# micromouse6_3.net
KiCad netlist of a schematic drawn in EAGLE
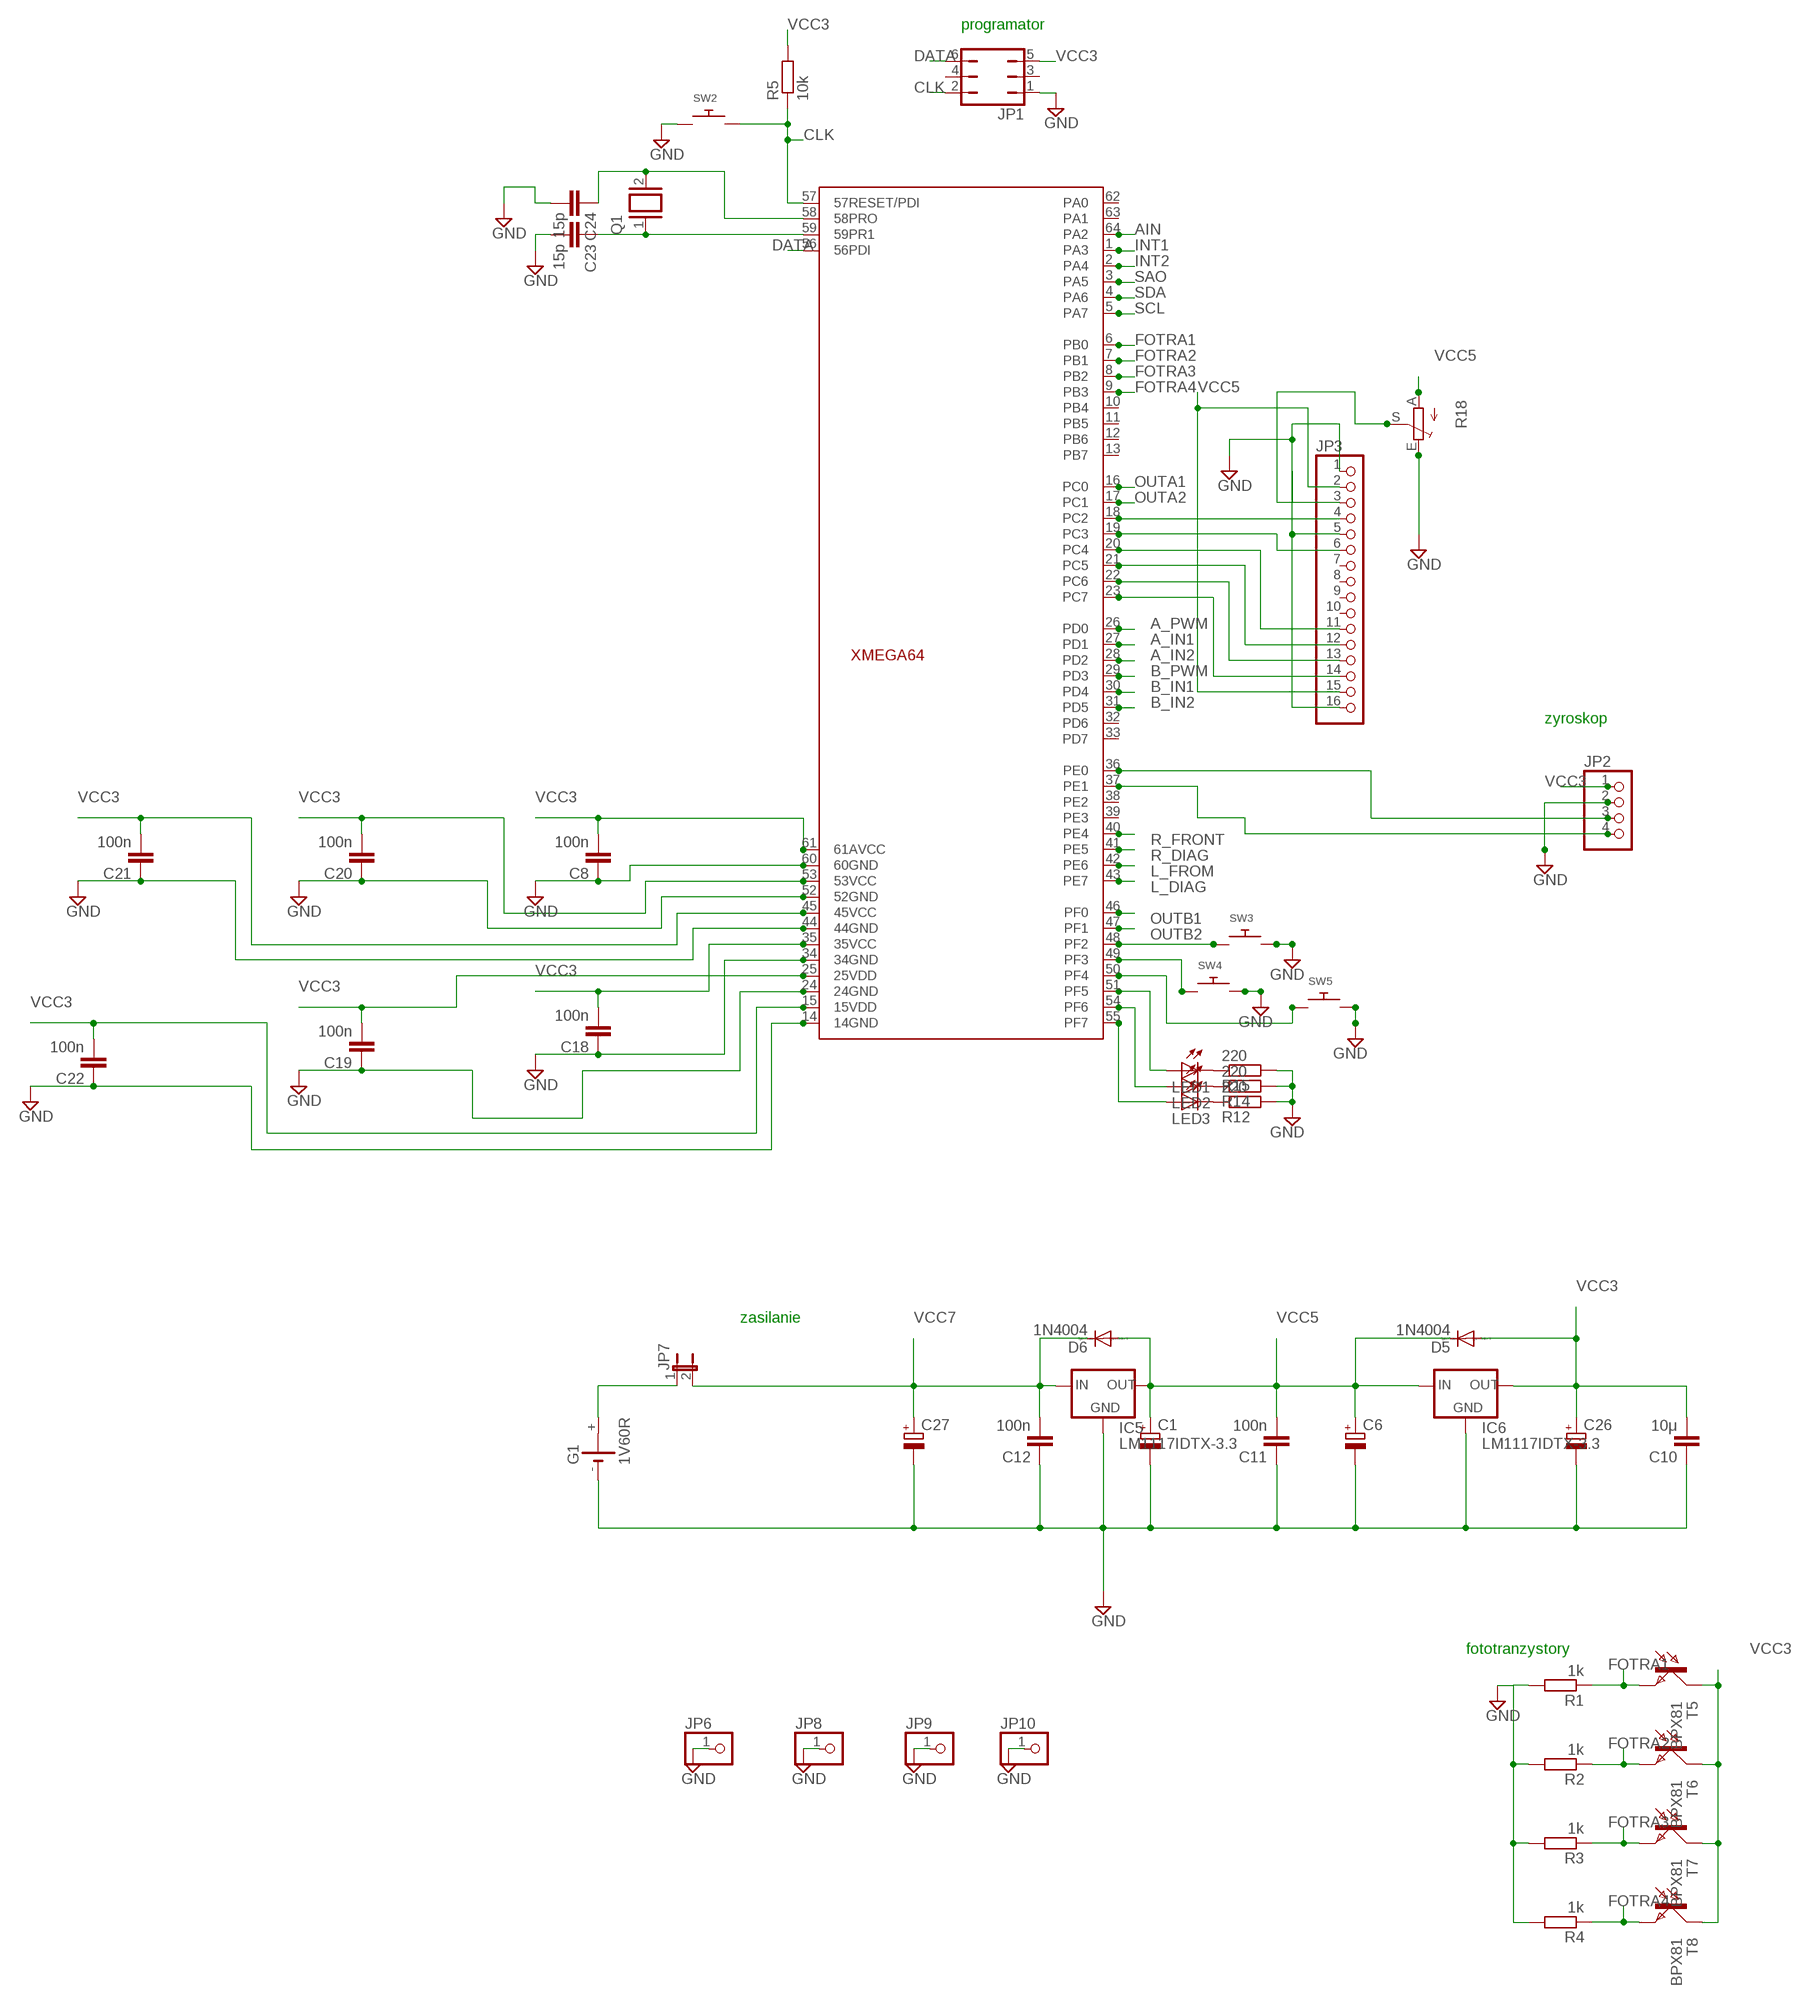
[diagram p0: schematic, sheet 1, part 1 of 2]
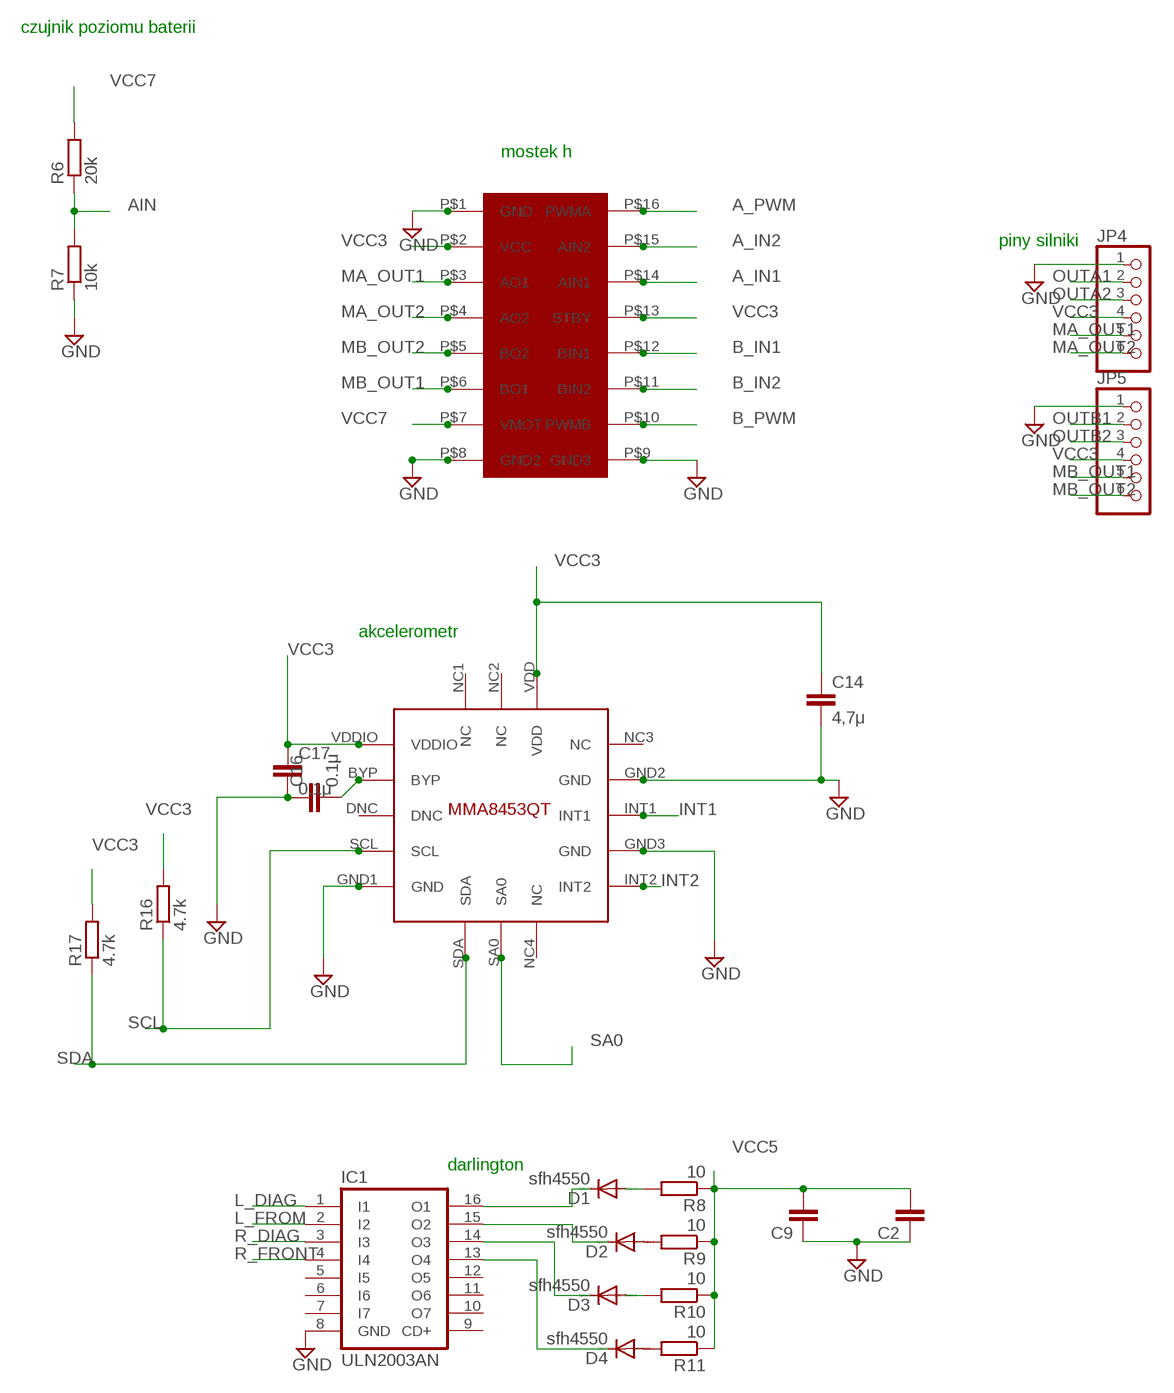
[diagram p1: schematic, sheet 1, part 2 of 2]

(export (version "E")
  (design (tool "Eeschema 10.0.6"))
  (components
    (comp (ref "ACC1")
      (value "MMA8453QT")
      (footprint "eagle-import:MMA8453QT")
      (libsource (lib "eagle-import") (part "MMA8453QT"))
    )
    (comp (ref "C1")
      (value "CPOL-EUE2.5-5")
      (footprint "eagle-import:E2,5-5")
      (libsource (lib "eagle-import") (part "CPOL-EUE2.5-5"))
    )
    (comp (ref "C2")
      (value "C-EU025-024X044")
      (footprint "eagle-import:C025-024X044")
      (libsource (lib "eagle-import") (part "C-EU025-024X044"))
    )
    (comp (ref "C6")
      (value "CPOL-EUE2.5-5")
      (footprint "eagle-import:E2,5-5")
      (libsource (lib "eagle-import") (part "CPOL-EUE2.5-5"))
    )
    (comp (ref "C8")
      (value "100n")
      (footprint "eagle-import:C025-024X044")
      (libsource (lib "eagle-import") (part "C-EU025-024X044"))
    )
    (comp (ref "C9")
      (value "C-EU025-024X044")
      (footprint "eagle-import:C025-024X044")
      (libsource (lib "eagle-import") (part "C-EU025-024X044"))
    )
    (comp (ref "C10")
      (value "10μ")
      (footprint "eagle-import:C025-024X044")
      (libsource (lib "eagle-import") (part "C-EU025-024X044"))
    )
    (comp (ref "C11")
      (value "100n")
      (footprint "eagle-import:C025-024X044")
      (libsource (lib "eagle-import") (part "C-EU025-024X044"))
    )
    (comp (ref "C12")
      (value "100n")
      (footprint "eagle-import:C025-024X044")
      (libsource (lib "eagle-import") (part "C-EU025-024X044"))
    )
    (comp (ref "C14")
      (value "4,7μ")
      (footprint "eagle-import:C025-024X044")
      (libsource (lib "eagle-import") (part "C-EU025-024X044"))
    )
    (comp (ref "C16")
      (value "0.1μ")
      (footprint "eagle-import:C025-024X044")
      (libsource (lib "eagle-import") (part "C-EU025-024X044"))
    )
    (comp (ref "C17")
      (value "0.1μ")
      (footprint "eagle-import:C025-024X044")
      (libsource (lib "eagle-import") (part "C-EU025-024X044"))
    )
    (comp (ref "C18")
      (value "100n")
      (footprint "eagle-import:C025-024X044")
      (libsource (lib "eagle-import") (part "C-EU025-024X044"))
    )
    (comp (ref "C19")
      (value "100n")
      (footprint "eagle-import:C025-024X044")
      (libsource (lib "eagle-import") (part "C-EU025-024X044"))
    )
    (comp (ref "C20")
      (value "100n")
      (footprint "eagle-import:C025-024X044")
      (libsource (lib "eagle-import") (part "C-EU025-024X044"))
    )
    (comp (ref "C21")
      (value "100n")
      (footprint "eagle-import:C025-024X044")
      (libsource (lib "eagle-import") (part "C-EU025-024X044"))
    )
    (comp (ref "C22")
      (value "100n")
      (footprint "eagle-import:C025-024X044")
      (libsource (lib "eagle-import") (part "C-EU025-024X044"))
    )
    (comp (ref "C23")
      (value "15p")
      (footprint "eagle-import:C025-024X044")
      (libsource (lib "eagle-import") (part "C-EU025-024X044"))
    )
    (comp (ref "C24")
      (value "15p")
      (footprint "eagle-import:C025-024X044")
      (libsource (lib "eagle-import") (part "C-EU025-024X044"))
    )
    (comp (ref "C26")
      (value "CPOL-EUE2.5-5")
      (footprint "eagle-import:E2,5-5")
      (libsource (lib "eagle-import") (part "CPOL-EUE2.5-5"))
    )
    (comp (ref "C27")
      (value "CPOL-EUE2.5-5")
      (footprint "eagle-import:E2,5-5")
      (libsource (lib "eagle-import") (part "CPOL-EUE2.5-5"))
    )
    (comp (ref "D1")
      (value "sfh4550")
      (footprint "eagle-import:DO41-10")
      (libsource (lib "eagle-import") (part "1N4004"))
    )
    (comp (ref "D2")
      (value "sfh4550")
      (footprint "eagle-import:DO41-10")
      (libsource (lib "eagle-import") (part "1N4004"))
    )
    (comp (ref "D3")
      (value "sfh4550")
      (footprint "eagle-import:DO41-10")
      (libsource (lib "eagle-import") (part "1N4004"))
    )
    (comp (ref "D4")
      (value "sfh4550")
      (footprint "eagle-import:DO41-10")
      (libsource (lib "eagle-import") (part "1N4004"))
    )
    (comp (ref "D5")
      (value "1N4004")
      (footprint "eagle-import:DO41-10")
      (libsource (lib "eagle-import") (part "1N4004"))
    )
    (comp (ref "D6")
      (value "1N4004")
      (footprint "eagle-import:DO41-10")
      (libsource (lib "eagle-import") (part "1N4004"))
    )
    (comp (ref "G1")
      (value "1V60R")
      (footprint "eagle-import:1V60R")
      (libsource (lib "eagle-import") (part "1V60R"))
    )
    (comp (ref "IC1")
      (value "ULN2003AN")
      (footprint "eagle-import:DIL16")
      (libsource (lib "eagle-import") (part "ULN2003AN"))
    )
    (comp (ref "IC5")
      (value "LM1117IDTX-3.3")
      (footprint "eagle-import:TO252")
      (libsource (lib "eagle-import") (part "LM1117IDTX-3.3"))
    )
    (comp (ref "IC6")
      (value "LM1117IDTX-3.3")
      (footprint "eagle-import:TO252")
      (libsource (lib "eagle-import") (part "LM1117IDTX-3.3"))
    )
    (comp (ref "JP1")
      (value "JP3Q")
      (footprint "eagle-import:JP3Q")
      (libsource (lib "eagle-import") (part "JP3Q"))
    )
    (comp (ref "JP2")
      (value "PINHD-1X4")
      (footprint "eagle-import:1X04")
      (libsource (lib "eagle-import") (part "PINHD-1X4"))
    )
    (comp (ref "JP3")
      (value "PINHD-1X16")
      (footprint "eagle-import:1X16")
      (libsource (lib "eagle-import") (part "PINHD-1X16"))
    )
    (comp (ref "JP4")
      (value "PINHD-1X6")
      (footprint "eagle-import:1X06")
      (libsource (lib "eagle-import") (part "PINHD-1X6"))
    )
    (comp (ref "JP5")
      (value "PINHD-1X6")
      (footprint "eagle-import:1X06")
      (libsource (lib "eagle-import") (part "PINHD-1X6"))
    )
    (comp (ref "JP6")
      (value "PINHD-1X1")
      (footprint "eagle-import:1X01")
      (libsource (lib "eagle-import") (part "PINHD-1X1"))
    )
    (comp (ref "JP7")
      (value "JP1E")
      (footprint "eagle-import:JP1")
      (libsource (lib "eagle-import") (part "JP1E"))
    )
    (comp (ref "JP8")
      (value "PINHD-1X1")
      (footprint "eagle-import:1X01")
      (libsource (lib "eagle-import") (part "PINHD-1X1"))
    )
    (comp (ref "JP9")
      (value "PINHD-1X1")
      (footprint "eagle-import:1X01")
      (libsource (lib "eagle-import") (part "PINHD-1X1"))
    )
    (comp (ref "JP10")
      (value "PINHD-1X1")
      (footprint "eagle-import:1X01")
      (libsource (lib "eagle-import") (part "PINHD-1X1"))
    )
    (comp (ref "LED1")
      (value "LEDSMT1206")
      (footprint "eagle-import:1206")
      (libsource (lib "eagle-import") (part "LEDSMT1206"))
    )
    (comp (ref "LED2")
      (value "LEDSMT1206")
      (footprint "eagle-import:1206")
      (libsource (lib "eagle-import") (part "LEDSMT1206"))
    )
    (comp (ref "LED3")
      (value "LEDSMT1206")
      (footprint "eagle-import:1206")
      (libsource (lib "eagle-import") (part "LEDSMT1206"))
    )
    (comp (ref "Q1")
      (value "XTAL/S")
      (footprint "eagle-import:QS")
      (libsource (lib "eagle-import") (part "XTAL/S"))
    )
    (comp (ref "R1")
      (value "1k")
      (footprint "eagle-import:R0805")
      (libsource (lib "eagle-import") (part "R-EU_R0805"))
    )
    (comp (ref "R2")
      (value "1k")
      (footprint "eagle-import:R0805")
      (libsource (lib "eagle-import") (part "R-EU_R0805"))
    )
    (comp (ref "R3")
      (value "1k")
      (footprint "eagle-import:R0805")
      (libsource (lib "eagle-import") (part "R-EU_R0805"))
    )
    (comp (ref "R4")
      (value "1k")
      (footprint "eagle-import:R0805")
      (libsource (lib "eagle-import") (part "R-EU_R0805"))
    )
    (comp (ref "R5")
      (value "10k")
      (footprint "eagle-import:R0805")
      (libsource (lib "eagle-import") (part "R-EU_R0805"))
    )
    (comp (ref "R6")
      (value "20k")
      (footprint "eagle-import:R0805")
      (libsource (lib "eagle-import") (part "R-EU_R0805"))
    )
    (comp (ref "R7")
      (value "10k")
      (footprint "eagle-import:R0805")
      (libsource (lib "eagle-import") (part "R-EU_R0805"))
    )
    (comp (ref "R8")
      (value "10")
      (footprint "eagle-import:R0805")
      (libsource (lib "eagle-import") (part "R-EU_R0805"))
    )
    (comp (ref "R9")
      (value "10")
      (footprint "eagle-import:R0805")
      (libsource (lib "eagle-import") (part "R-EU_R0805"))
    )
    (comp (ref "R10")
      (value "10")
      (footprint "eagle-import:R0805")
      (libsource (lib "eagle-import") (part "R-EU_R0805"))
    )
    (comp (ref "R11")
      (value "10")
      (footprint "eagle-import:R0805")
      (libsource (lib "eagle-import") (part "R-EU_R0805"))
    )
    (comp (ref "R12")
      (value "220")
      (footprint "eagle-import:R0805")
      (libsource (lib "eagle-import") (part "R-EU_R0805"))
    )
    (comp (ref "R14")
      (value "220")
      (footprint "eagle-import:R0805")
      (libsource (lib "eagle-import") (part "R-EU_R0805"))
    )
    (comp (ref "R15")
      (value "220")
      (footprint "eagle-import:R0805")
      (libsource (lib "eagle-import") (part "R-EU_R0805"))
    )
    (comp (ref "R16")
      (value "4.7k")
      (footprint "eagle-import:R0805")
      (libsource (lib "eagle-import") (part "R-EU_R0805"))
    )
    (comp (ref "R17")
      (value "4.7k")
      (footprint "eagle-import:R0805")
      (libsource (lib "eagle-import") (part "R-EU_R0805"))
    )
    (comp (ref "R18")
      (value "TRIM_EU-B25P")
      (footprint "eagle-import:B25P")
      (libsource (lib "eagle-import") (part "TRIM_EU-B25P"))
    )
    (comp (ref "SW2")
      (value "SWITCH_PUSHBUTTONEVQ-PE")
      (footprint "eagle-import:TACT_PANA-EVQ")
      (libsource (lib "eagle-import") (part "SWITCH_PUSHBUTTONEVQ-PE"))
    )
    (comp (ref "SW3")
      (value "SWITCH_PUSHBUTTONEVQ-PE")
      (footprint "eagle-import:TACT_PANA-EVQ")
      (libsource (lib "eagle-import") (part "SWITCH_PUSHBUTTONEVQ-PE"))
    )
    (comp (ref "SW4")
      (value "SWITCH_PUSHBUTTONEVQ-PE")
      (footprint "eagle-import:TACT_PANA-EVQ")
      (libsource (lib "eagle-import") (part "SWITCH_PUSHBUTTONEVQ-PE"))
    )
    (comp (ref "SW5")
      (value "SWITCH_PUSHBUTTONEVQ-PE")
      (footprint "eagle-import:TACT_PANA-EVQ")
      (libsource (lib "eagle-import") (part "SWITCH_PUSHBUTTONEVQ-PE"))
    )
    (comp (ref "T5")
      (value "BPX81")
      (footprint "eagle-import:BPX81")
      (libsource (lib "eagle-import") (part "BPX81"))
    )
    (comp (ref "T6")
      (value "BPX81")
      (footprint "eagle-import:BPX81")
      (libsource (lib "eagle-import") (part "BPX81"))
    )
    (comp (ref "T7")
      (value "BPX81")
      (footprint "eagle-import:BPX81")
      (libsource (lib "eagle-import") (part "BPX81"))
    )
    (comp (ref "T8")
      (value "BPX81")
      (footprint "eagle-import:BPX81")
      (libsource (lib "eagle-import") (part "BPX81"))
    )
    (comp (ref "U$1")
      (value "POLULU713")
      (footprint "eagle-import:POLULU713")
      (libsource (lib "eagle-import") (part "POLULU713"))
    )
    (comp (ref "XMEGA64")
      (value "XMEGA64C3TQFP64")
      (footprint "eagle-import:TQFP64")
      (libsource (lib "eagle-import") (part "XMEGA64C3TQFP64"))
    )
  )
  (nets
    (net (code "1") (name "/AIN") (class "Default")
      (node (ref "R6") (pin "1") (pinfunction "1_1") (pintype "passive"))
      (node (ref "R7") (pin "2") (pinfunction "2_2") (pintype "passive"))
      (node (ref "XMEGA64") (pin "64") (pinfunction "PA2_64") (pintype "bidirectional"))
    )
    (net (code "2") (name "/A_IN1") (class "Default")
      (node (ref "U$1") (pin "P$14") (pinfunction "AIN1_P$14") (pintype "bidirectional"))
      (node (ref "XMEGA64") (pin "27") (pinfunction "PD1_27") (pintype "bidirectional"))
    )
    (net (code "3") (name "/A_IN2") (class "Default")
      (node (ref "U$1") (pin "P$15") (pinfunction "AIN2_P$15") (pintype "bidirectional"))
      (node (ref "XMEGA64") (pin "28") (pinfunction "PD2_28") (pintype "bidirectional"))
    )
    (net (code "4") (name "/A_PWM") (class "Default")
      (node (ref "U$1") (pin "P$16") (pinfunction "PWMA_P$16") (pintype "bidirectional"))
      (node (ref "XMEGA64") (pin "26") (pinfunction "PD0_26") (pintype "bidirectional"))
    )
    (net (code "5") (name "/B_IN1") (class "Default")
      (node (ref "U$1") (pin "P$12") (pinfunction "BIN1_P$12") (pintype "bidirectional"))
      (node (ref "XMEGA64") (pin "30") (pinfunction "PD4_30") (pintype "bidirectional"))
    )
    (net (code "6") (name "/B_IN2") (class "Default")
      (node (ref "U$1") (pin "P$11") (pinfunction "BIN2_P$11") (pintype "bidirectional"))
      (node (ref "XMEGA64") (pin "31") (pinfunction "PD5_31") (pintype "bidirectional"))
    )
    (net (code "7") (name "/B_PWM") (class "Default")
      (node (ref "U$1") (pin "P$10") (pinfunction "PWMB_P$10") (pintype "bidirectional"))
      (node (ref "XMEGA64") (pin "29") (pinfunction "PD3_29") (pintype "bidirectional"))
    )
    (net (code "8") (name "/CLK") (class "Default")
      (node (ref "JP1") (pin "2") (pinfunction "2_2") (pintype "passive"))
      (node (ref "R5") (pin "1") (pinfunction "1_1") (pintype "passive"))
      (node (ref "SW2") (pin "P$2") (pinfunction "P$2_P$2") (pintype "passive"))
      (node (ref "XMEGA64") (pin "57") (pinfunction "57RESET/PDI_57") (pintype "bidirectional"))
    )
    (net (code "9") (name "/DATA") (class "Default")
      (node (ref "JP1") (pin "6") (pinfunction "6_6") (pintype "passive"))
      (node (ref "XMEGA64") (pin "56") (pinfunction "56PDI_56") (pintype "bidirectional"))
    )
    (net (code "10") (name "/FOTRA1") (class "Default")
      (node (ref "R1") (pin "1") (pinfunction "1_1") (pintype "passive"))
      (node (ref "T5") (pin "E") (pinfunction "E_E") (pintype "passive"))
      (node (ref "XMEGA64") (pin "6") (pinfunction "PB0_6") (pintype "bidirectional"))
    )
    (net (code "11") (name "/FOTRA2") (class "Default")
      (node (ref "R2") (pin "1") (pinfunction "1_1") (pintype "passive"))
      (node (ref "T6") (pin "E") (pinfunction "E_E") (pintype "passive"))
      (node (ref "XMEGA64") (pin "7") (pinfunction "PB1_7") (pintype "bidirectional"))
    )
    (net (code "12") (name "/FOTRA3") (class "Default")
      (node (ref "R3") (pin "1") (pinfunction "1_1") (pintype "passive"))
      (node (ref "T7") (pin "E") (pinfunction "E_E") (pintype "passive"))
      (node (ref "XMEGA64") (pin "8") (pinfunction "PB2_8") (pintype "bidirectional"))
    )
    (net (code "13") (name "/FOTRA4") (class "Default")
      (node (ref "R4") (pin "1") (pinfunction "1_1") (pintype "passive"))
      (node (ref "T8") (pin "E") (pinfunction "E_E") (pintype "passive"))
      (node (ref "XMEGA64") (pin "9") (pinfunction "PB3_9") (pintype "bidirectional"))
    )
    (net (code "14") (name "/INT1") (class "Default")
      (node (ref "ACC1") (pin "INT1") (pinfunction "INT1_INT1") (pintype "output"))
      (node (ref "XMEGA64") (pin "1") (pinfunction "PA3_1") (pintype "bidirectional"))
    )
    (net (code "15") (name "/INT2") (class "Default")
      (node (ref "ACC1") (pin "INT2") (pinfunction "INT2_INT2") (pintype "output"))
      (node (ref "XMEGA64") (pin "2") (pinfunction "PA4_2") (pintype "bidirectional"))
    )
    (net (code "16") (name "/L_DIAG") (class "Default")
      (node (ref "IC1") (pin "1") (pinfunction "I1_1") (pintype "input"))
      (node (ref "XMEGA64") (pin "43") (pinfunction "PE7_43") (pintype "bidirectional"))
    )
    (net (code "17") (name "/L_FROM") (class "Default")
      (node (ref "IC1") (pin "2") (pinfunction "I2_2") (pintype "input"))
      (node (ref "XMEGA64") (pin "42") (pinfunction "PE6_42") (pintype "bidirectional"))
    )
    (net (code "18") (name "/MA_OUT1") (class "Default")
      (node (ref "JP4") (pin "5") (pinfunction "5_5") (pintype "passive"))
      (node (ref "U$1") (pin "P$3") (pinfunction "AO1_P$3") (pintype "bidirectional"))
    )
    (net (code "19") (name "/MA_OUT2") (class "Default")
      (node (ref "JP4") (pin "6") (pinfunction "6_6") (pintype "passive"))
      (node (ref "U$1") (pin "P$4") (pinfunction "AO2_P$4") (pintype "bidirectional"))
    )
    (net (code "20") (name "/MB_OUT1") (class "Default")
      (node (ref "JP5") (pin "5") (pinfunction "5_5") (pintype "passive"))
      (node (ref "U$1") (pin "P$6") (pinfunction "BO1_P$6") (pintype "bidirectional"))
    )
    (net (code "21") (name "/MB_OUT2") (class "Default")
      (node (ref "JP5") (pin "6") (pinfunction "6_6") (pintype "passive"))
      (node (ref "U$1") (pin "P$5") (pinfunction "BO2_P$5") (pintype "bidirectional"))
    )
    (net (code "22") (name "/OUTA1") (class "Default")
      (node (ref "JP4") (pin "2") (pinfunction "2_2") (pintype "passive"))
      (node (ref "XMEGA64") (pin "16") (pinfunction "PC0_16") (pintype "bidirectional"))
    )
    (net (code "23") (name "/OUTA2") (class "Default")
      (node (ref "JP4") (pin "3") (pinfunction "3_3") (pintype "passive"))
      (node (ref "XMEGA64") (pin "17") (pinfunction "PC1_17") (pintype "bidirectional"))
    )
    (net (code "24") (name "/OUTB1") (class "Default")
      (node (ref "JP5") (pin "2") (pinfunction "2_2") (pintype "passive"))
      (node (ref "XMEGA64") (pin "46") (pinfunction "PF0_46") (pintype "bidirectional"))
    )
    (net (code "25") (name "/OUTB2") (class "Default")
      (node (ref "JP5") (pin "3") (pinfunction "3_3") (pintype "passive"))
      (node (ref "XMEGA64") (pin "47") (pinfunction "PF1_47") (pintype "bidirectional"))
    )
    (net (code "26") (name "/R_DIAG") (class "Default")
      (node (ref "IC1") (pin "3") (pinfunction "I3_3") (pintype "input"))
      (node (ref "XMEGA64") (pin "41") (pinfunction "PE5_41") (pintype "bidirectional"))
    )
    (net (code "27") (name "/R_FRONT") (class "Default")
      (node (ref "IC1") (pin "4") (pinfunction "I4_4") (pintype "input"))
      (node (ref "XMEGA64") (pin "40") (pinfunction "PE4_40") (pintype "bidirectional"))
    )
    (net (code "28") (name "/SA0") (class "Default")
      (node (ref "ACC1") (pin "SA0") (pinfunction "SA0_SA0") (pintype "bidirectional"))
    )
    (net (code "29") (name "/SAO") (class "Default")
      (node (ref "XMEGA64") (pin "3") (pinfunction "PA5_3") (pintype "bidirectional"))
    )
    (net (code "30") (name "/SCL") (class "Default")
      (node (ref "ACC1") (pin "SCL") (pinfunction "SCL_SCL") (pintype "bidirectional"))
      (node (ref "R16") (pin "1") (pinfunction "1_1") (pintype "passive"))
      (node (ref "XMEGA64") (pin "5") (pinfunction "PA7_5") (pintype "bidirectional"))
    )
    (net (code "31") (name "/SDA") (class "Default")
      (node (ref "ACC1") (pin "SDA") (pinfunction "SDA_SDA") (pintype "bidirectional"))
      (node (ref "R17") (pin "1") (pinfunction "1_1") (pintype "passive"))
      (node (ref "XMEGA64") (pin "4") (pinfunction "PA6_4") (pintype "bidirectional"))
    )
    (net (code "32") (name "/VCC3") (class "Default")
      (node (ref "ACC1") (pin "VDD") (pinfunction "VDD_VDD") (pintype "power_in"))
      (node (ref "ACC1") (pin "VDDIO") (pinfunction "VDDIO_VDDIO") (pintype "power_in"))
      (node (ref "C10") (pin "2") (pinfunction "2_2") (pintype "passive"))
      (node (ref "C14") (pin "1") (pinfunction "1_1") (pintype "passive"))
      (node (ref "C17") (pin "1") (pinfunction "1_1") (pintype "passive"))
      (node (ref "C18") (pin "2") (pinfunction "2_2") (pintype "passive"))
      (node (ref "C19") (pin "2") (pinfunction "2_2") (pintype "passive"))
      (node (ref "C20") (pin "2") (pinfunction "2_2") (pintype "passive"))
      (node (ref "C21") (pin "2") (pinfunction "2_2") (pintype "passive"))
      (node (ref "C22") (pin "2") (pinfunction "2_2") (pintype "passive"))
      (node (ref "C26") (pin "+") (pinfunction "+_+") (pintype "passive"))
      (node (ref "C8") (pin "2") (pinfunction "2_2") (pintype "passive"))
      (node (ref "D5") (pin "A") (pinfunction "A_A") (pintype "passive"))
      (node (ref "IC6") (pin "TAB") (pinfunction "OUT_TAB") (pintype "passive"))
      (node (ref "JP1") (pin "5") (pinfunction "5_5") (pintype "passive"))
      (node (ref "JP2") (pin "1") (pinfunction "1_1") (pintype "passive"))
      (node (ref "JP4") (pin "4") (pinfunction "4_4") (pintype "passive"))
      (node (ref "JP5") (pin "4") (pinfunction "4_4") (pintype "passive"))
      (node (ref "R16") (pin "2") (pinfunction "2_2") (pintype "passive"))
      (node (ref "R17") (pin "2") (pinfunction "2_2") (pintype "passive"))
      (node (ref "R5") (pin "2") (pinfunction "2_2") (pintype "passive"))
      (node (ref "T5") (pin "C") (pinfunction "C_C") (pintype "passive"))
      (node (ref "T6") (pin "C") (pinfunction "C_C") (pintype "passive"))
      (node (ref "T7") (pin "C") (pinfunction "C_C") (pintype "passive"))
      (node (ref "T8") (pin "C") (pinfunction "C_C") (pintype "passive"))
      (node (ref "U$1") (pin "P$13") (pinfunction "STBY_P$13") (pintype "bidirectional"))
      (node (ref "U$1") (pin "P$2") (pinfunction "VCC_P$2") (pintype "bidirectional"))
      (node (ref "XMEGA64") (pin "15") (pinfunction "15VDD_15") (pintype "power_in"))
      (node (ref "XMEGA64") (pin "25") (pinfunction "25VDD_25") (pintype "power_in"))
      (node (ref "XMEGA64") (pin "35") (pinfunction "35VCC_35") (pintype "power_in"))
      (node (ref "XMEGA64") (pin "45") (pinfunction "45VCC_45") (pintype "power_in"))
      (node (ref "XMEGA64") (pin "53") (pinfunction "53VCC_53") (pintype "power_in"))
      (node (ref "XMEGA64") (pin "61") (pinfunction "61AVCC_61") (pintype "power_in"))
    )
    (net (code "33") (name "/VCC5") (class "Default")
      (node (ref "C1") (pin "+") (pinfunction "+_+") (pintype "passive"))
      (node (ref "C11") (pin "2") (pinfunction "2_2") (pintype "passive"))
      (node (ref "C2") (pin "2") (pinfunction "2_2") (pintype "passive"))
      (node (ref "C6") (pin "+") (pinfunction "+_+") (pintype "passive"))
      (node (ref "C9") (pin "2") (pinfunction "2_2") (pintype "passive"))
      (node (ref "D5") (pin "C") (pinfunction "C_C") (pintype "passive"))
      (node (ref "D6") (pin "A") (pinfunction "A_A") (pintype "passive"))
      (node (ref "IC5") (pin "TAB") (pinfunction "OUT_TAB") (pintype "passive"))
      (node (ref "IC6") (pin "2") (pinfunction "IN_2") (pintype "input"))
      (node (ref "JP3") (pin "15") (pinfunction "15_15") (pintype "passive"))
      (node (ref "JP3") (pin "2") (pinfunction "2_2") (pintype "passive"))
      (node (ref "R10") (pin "1") (pinfunction "1_1") (pintype "passive"))
      (node (ref "R11") (pin "1") (pinfunction "1_1") (pintype "passive"))
      (node (ref "R18") (pin "A") (pinfunction "A_A") (pintype "passive"))
      (node (ref "R8") (pin "1") (pinfunction "1_1") (pintype "passive"))
      (node (ref "R9") (pin "1") (pinfunction "1_1") (pintype "passive"))
    )
    (net (code "34") (name "/VCC7") (class "Default")
      (node (ref "C12") (pin "2") (pinfunction "2_2") (pintype "passive"))
      (node (ref "C27") (pin "+") (pinfunction "+_+") (pintype "passive"))
      (node (ref "D6") (pin "C") (pinfunction "C_C") (pintype "passive"))
      (node (ref "IC5") (pin "2") (pinfunction "IN_2") (pintype "input"))
      (node (ref "JP7") (pin "2") (pinfunction "2_2") (pintype "passive"))
      (node (ref "R6") (pin "2") (pinfunction "2_2") (pintype "passive"))
      (node (ref "U$1") (pin "P$7") (pinfunction "VMOT_P$7") (pintype "bidirectional"))
    )
    (net (code "35") (name "GND") (class "Default")
      (node (ref "ACC1") (pin "GND1") (pinfunction "GND_GND1") (pintype "power_in"))
      (node (ref "ACC1") (pin "GND2") (pinfunction "GND_GND2") (pintype "power_in"))
      (node (ref "ACC1") (pin "GND3") (pinfunction "GND_GND3") (pintype "power_in"))
      (node (ref "C1") (pin "-") (pinfunction "-_-") (pintype "passive"))
      (node (ref "C10") (pin "1") (pinfunction "1_1") (pintype "passive"))
      (node (ref "C11") (pin "1") (pinfunction "1_1") (pintype "passive"))
      (node (ref "C12") (pin "1") (pinfunction "1_1") (pintype "passive"))
      (node (ref "C14") (pin "2") (pinfunction "2_2") (pintype "passive"))
      (node (ref "C16") (pin "1") (pinfunction "1_1") (pintype "passive"))
      (node (ref "C17") (pin "2") (pinfunction "2_2") (pintype "passive"))
      (node (ref "C18") (pin "1") (pinfunction "1_1") (pintype "passive"))
      (node (ref "C19") (pin "1") (pinfunction "1_1") (pintype "passive"))
      (node (ref "C2") (pin "1") (pinfunction "1_1") (pintype "passive"))
      (node (ref "C20") (pin "1") (pinfunction "1_1") (pintype "passive"))
      (node (ref "C21") (pin "1") (pinfunction "1_1") (pintype "passive"))
      (node (ref "C22") (pin "1") (pinfunction "1_1") (pintype "passive"))
      (node (ref "C23") (pin "2") (pinfunction "2_2") (pintype "passive"))
      (node (ref "C24") (pin "2") (pinfunction "2_2") (pintype "passive"))
      (node (ref "C26") (pin "-") (pinfunction "-_-") (pintype "passive"))
      (node (ref "C27") (pin "-") (pinfunction "-_-") (pintype "passive"))
      (node (ref "C6") (pin "-") (pinfunction "-_-") (pintype "passive"))
      (node (ref "C8") (pin "1") (pinfunction "1_1") (pintype "passive"))
      (node (ref "C9") (pin "1") (pinfunction "1_1") (pintype "passive"))
      (node (ref "G1") (pin "-") (pinfunction "-_-") (pintype "passive"))
      (node (ref "IC1") (pin "8") (pinfunction "GND_8") (pintype "power_in"))
      (node (ref "IC5") (pin "1") (pinfunction "GND_1") (pintype "input"))
      (node (ref "IC6") (pin "1") (pinfunction "GND_1") (pintype "input"))
      (node (ref "JP1") (pin "1") (pinfunction "1_1") (pintype "passive"))
      (node (ref "JP10") (pin "1") (pinfunction "1_1") (pintype "passive"))
      (node (ref "JP2") (pin "2") (pinfunction "2_2") (pintype "passive"))
      (node (ref "JP3") (pin "1") (pinfunction "1_1") (pintype "passive"))
      (node (ref "JP3") (pin "16") (pinfunction "16_16") (pintype "passive"))
      (node (ref "JP3") (pin "5") (pinfunction "5_5") (pintype "passive"))
      (node (ref "JP4") (pin "1") (pinfunction "1_1") (pintype "passive"))
      (node (ref "JP5") (pin "1") (pinfunction "1_1") (pintype "passive"))
      (node (ref "JP6") (pin "1") (pinfunction "1_1") (pintype "passive"))
      (node (ref "JP8") (pin "1") (pinfunction "1_1") (pintype "passive"))
      (node (ref "JP9") (pin "1") (pinfunction "1_1") (pintype "passive"))
      (node (ref "R1") (pin "2") (pinfunction "2_2") (pintype "passive"))
      (node (ref "R12") (pin "2") (pinfunction "2_2") (pintype "passive"))
      (node (ref "R14") (pin "2") (pinfunction "2_2") (pintype "passive"))
      (node (ref "R15") (pin "2") (pinfunction "2_2") (pintype "passive"))
      (node (ref "R18") (pin "E") (pinfunction "E_E") (pintype "passive"))
      (node (ref "R2") (pin "2") (pinfunction "2_2") (pintype "passive"))
      (node (ref "R3") (pin "2") (pinfunction "2_2") (pintype "passive"))
      (node (ref "R4") (pin "2") (pinfunction "2_2") (pintype "passive"))
      (node (ref "R7") (pin "1") (pinfunction "1_1") (pintype "passive"))
      (node (ref "SW2") (pin "P$1") (pinfunction "P$1_P$1") (pintype "passive"))
      (node (ref "SW3") (pin "P$2") (pinfunction "P$2_P$2") (pintype "passive"))
      (node (ref "SW4") (pin "P$2") (pinfunction "P$2_P$2") (pintype "passive"))
      (node (ref "SW5") (pin "P$2") (pinfunction "P$2_P$2") (pintype "passive"))
      (node (ref "U$1") (pin "P$1") (pinfunction "GND_P$1") (pintype "bidirectional"))
      (node (ref "U$1") (pin "P$8") (pinfunction "GND2_P$8") (pintype "bidirectional"))
      (node (ref "U$1") (pin "P$9") (pinfunction "GND3_P$9") (pintype "bidirectional"))
      (node (ref "XMEGA64") (pin "14") (pinfunction "14GND_14") (pintype "power_in"))
      (node (ref "XMEGA64") (pin "24") (pinfunction "24GND_24") (pintype "power_in"))
      (node (ref "XMEGA64") (pin "34") (pinfunction "34GND_34") (pintype "power_in"))
      (node (ref "XMEGA64") (pin "44") (pinfunction "44GND_44") (pintype "power_in"))
      (node (ref "XMEGA64") (pin "52") (pinfunction "52GND_52") (pintype "power_in"))
      (node (ref "XMEGA64") (pin "60") (pinfunction "60GND_60") (pintype "power_in"))
    )
    (net (code "36") (name "Net-(ACC1-PadBYP)") (class "Default")
      (node (ref "ACC1") (pin "BYP") (pinfunction "BYP_BYP") (pintype "passive"))
      (node (ref "C16") (pin "2") (pinfunction "2_2") (pintype "passive"))
    )
    (net (code "37") (name "Net-(D1-PadA)") (class "Default")
      (node (ref "D1") (pin "A") (pinfunction "A_A") (pintype "passive"))
      (node (ref "R8") (pin "2") (pinfunction "2_2") (pintype "passive"))
    )
    (net (code "38") (name "Net-(D2-PadA)") (class "Default")
      (node (ref "D2") (pin "A") (pinfunction "A_A") (pintype "passive"))
      (node (ref "R9") (pin "2") (pinfunction "2_2") (pintype "passive"))
    )
    (net (code "39") (name "Net-(D3-PadA)") (class "Default")
      (node (ref "D3") (pin "A") (pinfunction "A_A") (pintype "passive"))
      (node (ref "R10") (pin "2") (pinfunction "2_2") (pintype "passive"))
    )
    (net (code "40") (name "Net-(D4-PadA)") (class "Default")
      (node (ref "D4") (pin "A") (pinfunction "A_A") (pintype "passive"))
      (node (ref "R11") (pin "2") (pinfunction "2_2") (pintype "passive"))
    )
    (net (code "41") (name "Net-(G1-Pad+)") (class "Default")
      (node (ref "G1") (pin "+") (pinfunction "+_+") (pintype "passive"))
      (node (ref "JP7") (pin "1") (pinfunction "1_1") (pintype "passive"))
    )
    (net (code "42") (name "Net-(IC1-O1)") (class "Default")
      (node (ref "D1") (pin "C") (pinfunction "C_C") (pintype "passive"))
      (node (ref "IC1") (pin "16") (pinfunction "O1_16") (pintype "open_collector"))
    )
    (net (code "43") (name "Net-(IC1-O2)") (class "Default")
      (node (ref "D2") (pin "C") (pinfunction "C_C") (pintype "passive"))
      (node (ref "IC1") (pin "15") (pinfunction "O2_15") (pintype "open_collector"))
    )
    (net (code "44") (name "Net-(IC1-O3)") (class "Default")
      (node (ref "D3") (pin "C") (pinfunction "C_C") (pintype "passive"))
      (node (ref "IC1") (pin "14") (pinfunction "O3_14") (pintype "open_collector"))
    )
    (net (code "45") (name "Net-(IC1-O4)") (class "Default")
      (node (ref "D4") (pin "C") (pinfunction "C_C") (pintype "passive"))
      (node (ref "IC1") (pin "13") (pinfunction "O4_13") (pintype "open_collector"))
    )
    (net (code "46") (name "Net-(JP3-Pad3)") (class "Default")
      (node (ref "JP3") (pin "3") (pinfunction "3_3") (pintype "passive"))
      (node (ref "R18") (pin "S") (pinfunction "S_S") (pintype "passive"))
    )
    (net (code "47") (name "Net-(LED1-PadC)") (class "Default")
      (node (ref "LED1") (pin "C") (pinfunction "C_C") (pintype "passive"))
      (node (ref "R15") (pin "1") (pinfunction "1_1") (pintype "passive"))
    )
    (net (code "48") (name "Net-(LED2-PadC)") (class "Default")
      (node (ref "LED2") (pin "C") (pinfunction "C_C") (pintype "passive"))
      (node (ref "R14") (pin "1") (pinfunction "1_1") (pintype "passive"))
    )
    (net (code "49") (name "Net-(LED3-PadC)") (class "Default")
      (node (ref "LED3") (pin "C") (pinfunction "C_C") (pintype "passive"))
      (node (ref "R12") (pin "1") (pinfunction "1_1") (pintype "passive"))
    )
    (net (code "50") (name "Net-(XMEGA64-58PRO)") (class "Default")
      (node (ref "C24") (pin "1") (pinfunction "1_1") (pintype "passive"))
      (node (ref "Q1") (pin "2") (pinfunction "2_2") (pintype "passive"))
      (node (ref "XMEGA64") (pin "58") (pinfunction "58PRO_58") (pintype "bidirectional"))
    )
    (net (code "51") (name "Net-(XMEGA64-59PR1)") (class "Default")
      (node (ref "C23") (pin "1") (pinfunction "1_1") (pintype "passive"))
      (node (ref "Q1") (pin "1") (pinfunction "1_1") (pintype "passive"))
      (node (ref "XMEGA64") (pin "59") (pinfunction "59PR1_59") (pintype "bidirectional"))
    )
    (net (code "52") (name "Net-(XMEGA64-PC2)") (class "Default")
      (node (ref "JP3") (pin "4") (pinfunction "4_4") (pintype "passive"))
      (node (ref "XMEGA64") (pin "18") (pinfunction "PC2_18") (pintype "bidirectional"))
    )
    (net (code "53") (name "Net-(XMEGA64-PC3)") (class "Default")
      (node (ref "JP3") (pin "6") (pinfunction "6_6") (pintype "passive"))
      (node (ref "XMEGA64") (pin "19") (pinfunction "PC3_19") (pintype "bidirectional"))
    )
    (net (code "54") (name "Net-(XMEGA64-PC4)") (class "Default")
      (node (ref "JP3") (pin "11") (pinfunction "11_11") (pintype "passive"))
      (node (ref "XMEGA64") (pin "20") (pinfunction "PC4_20") (pintype "bidirectional"))
    )
    (net (code "55") (name "Net-(XMEGA64-PC5)") (class "Default")
      (node (ref "JP3") (pin "12") (pinfunction "12_12") (pintype "passive"))
      (node (ref "XMEGA64") (pin "21") (pinfunction "PC5_21") (pintype "bidirectional"))
    )
    (net (code "56") (name "Net-(XMEGA64-PC6)") (class "Default")
      (node (ref "JP3") (pin "13") (pinfunction "13_13") (pintype "passive"))
      (node (ref "XMEGA64") (pin "22") (pinfunction "PC6_22") (pintype "bidirectional"))
    )
    (net (code "57") (name "Net-(XMEGA64-PC7)") (class "Default")
      (node (ref "JP3") (pin "14") (pinfunction "14_14") (pintype "passive"))
      (node (ref "XMEGA64") (pin "23") (pinfunction "PC7_23") (pintype "bidirectional"))
    )
    (net (code "58") (name "Net-(XMEGA64-PE0)") (class "Default")
      (node (ref "JP2") (pin "3") (pinfunction "3_3") (pintype "passive"))
      (node (ref "XMEGA64") (pin "36") (pinfunction "PE0_36") (pintype "bidirectional"))
    )
    (net (code "59") (name "Net-(XMEGA64-PE1)") (class "Default")
      (node (ref "JP2") (pin "4") (pinfunction "4_4") (pintype "passive"))
      (node (ref "XMEGA64") (pin "37") (pinfunction "PE1_37") (pintype "bidirectional"))
    )
    (net (code "60") (name "Net-(XMEGA64-PF2)") (class "Default")
      (node (ref "SW3") (pin "P$1") (pinfunction "P$1_P$1") (pintype "passive"))
      (node (ref "XMEGA64") (pin "48") (pinfunction "PF2_48") (pintype "bidirectional"))
    )
    (net (code "61") (name "Net-(XMEGA64-PF3)") (class "Default")
      (node (ref "SW4") (pin "P$1") (pinfunction "P$1_P$1") (pintype "passive"))
      (node (ref "XMEGA64") (pin "49") (pinfunction "PF3_49") (pintype "bidirectional"))
    )
    (net (code "62") (name "Net-(XMEGA64-PF4)") (class "Default")
      (node (ref "SW5") (pin "P$1") (pinfunction "P$1_P$1") (pintype "passive"))
      (node (ref "XMEGA64") (pin "50") (pinfunction "PF4_50") (pintype "bidirectional"))
    )
    (net (code "63") (name "Net-(XMEGA64-PF5)") (class "Default")
      (node (ref "LED1") (pin "A") (pinfunction "A_A") (pintype "passive"))
      (node (ref "XMEGA64") (pin "51") (pinfunction "PF5_51") (pintype "bidirectional"))
    )
    (net (code "64") (name "Net-(XMEGA64-PF6)") (class "Default")
      (node (ref "LED2") (pin "A") (pinfunction "A_A") (pintype "passive"))
      (node (ref "XMEGA64") (pin "54") (pinfunction "PF6_54") (pintype "bidirectional"))
    )
    (net (code "65") (name "Net-(XMEGA64-PF7)") (class "Default")
      (node (ref "LED3") (pin "A") (pinfunction "A_A") (pintype "passive"))
      (node (ref "XMEGA64") (pin "55") (pinfunction "PF7_55") (pintype "bidirectional"))
    )
    (net (code "66") (name "unconnected-(ACC1-NC-PadNC1)") (class "Default")
      (node (ref "ACC1") (pin "NC1") (pinfunction "NC_NC1") (pintype "bidirectional"))
    )
    (net (code "67") (name "unconnected-(ACC1-NC-PadNC2)") (class "Default")
      (node (ref "ACC1") (pin "NC2") (pinfunction "NC_NC2") (pintype "bidirectional"))
    )
    (net (code "68") (name "unconnected-(ACC1-NC-PadNC3)") (class "Default")
      (node (ref "ACC1") (pin "NC3") (pinfunction "NC_NC3") (pintype "bidirectional"))
    )
    (net (code "69") (name "unconnected-(ACC1-NC-PadNC4)") (class "Default")
      (node (ref "ACC1") (pin "NC4") (pinfunction "NC_NC4") (pintype "bidirectional"))
    )
    (net (code "70") (name "unconnected-(ACC1-PadDNC)") (class "Default")
      (node (ref "ACC1") (pin "DNC") (pinfunction "DNC_DNC") (pintype "no_connect"))
    )
    (net (code "71") (name "unconnected-(G1-+-Pad+@1)") (class "Default")
      (node (ref "G1") (pin "+@1") (pinfunction "+_+@1") (pintype "passive"))
    )
    (net (code "72") (name "unconnected-(IC1-CD+-Pad9)") (class "Default")
      (node (ref "IC1") (pin "9") (pinfunction "CD+_9") (pintype "passive"))
    )
    (net (code "73") (name "unconnected-(IC1-I5-Pad5)") (class "Default")
      (node (ref "IC1") (pin "5") (pinfunction "I5_5") (pintype "input"))
    )
    (net (code "74") (name "unconnected-(IC1-I6-Pad6)") (class "Default")
      (node (ref "IC1") (pin "6") (pinfunction "I6_6") (pintype "input"))
    )
    (net (code "75") (name "unconnected-(IC1-I7-Pad7)") (class "Default")
      (node (ref "IC1") (pin "7") (pinfunction "I7_7") (pintype "input"))
    )
    (net (code "76") (name "unconnected-(IC1-O5-Pad12)") (class "Default")
      (node (ref "IC1") (pin "12") (pinfunction "O5_12") (pintype "open_collector"))
    )
    (net (code "77") (name "unconnected-(IC1-O6-Pad11)") (class "Default")
      (node (ref "IC1") (pin "11") (pinfunction "O6_11") (pintype "open_collector"))
    )
    (net (code "78") (name "unconnected-(IC1-O7-Pad10)") (class "Default")
      (node (ref "IC1") (pin "10") (pinfunction "O7_10") (pintype "open_collector"))
    )
    (net (code "79") (name "unconnected-(JP1-Pad3)") (class "Default")
      (node (ref "JP1") (pin "3") (pinfunction "3_3") (pintype "passive"))
    )
    (net (code "80") (name "unconnected-(JP1-Pad4)") (class "Default")
      (node (ref "JP1") (pin "4") (pinfunction "4_4") (pintype "passive"))
    )
    (net (code "81") (name "unconnected-(JP3-Pad7)") (class "Default")
      (node (ref "JP3") (pin "7") (pinfunction "7_7") (pintype "passive"))
    )
    (net (code "82") (name "unconnected-(JP3-Pad8)") (class "Default")
      (node (ref "JP3") (pin "8") (pinfunction "8_8") (pintype "passive"))
    )
    (net (code "83") (name "unconnected-(JP3-Pad9)") (class "Default")
      (node (ref "JP3") (pin "9") (pinfunction "9_9") (pintype "passive"))
    )
    (net (code "84") (name "unconnected-(JP3-Pad10)") (class "Default")
      (node (ref "JP3") (pin "10") (pinfunction "10_10") (pintype "passive"))
    )
    (net (code "85") (name "unconnected-(XMEGA64-PA0-Pad62)") (class "Default")
      (node (ref "XMEGA64") (pin "62") (pinfunction "PA0_62") (pintype "bidirectional"))
    )
    (net (code "86") (name "unconnected-(XMEGA64-PA1-Pad63)") (class "Default")
      (node (ref "XMEGA64") (pin "63") (pinfunction "PA1_63") (pintype "bidirectional"))
    )
    (net (code "87") (name "unconnected-(XMEGA64-PB4-Pad10)") (class "Default")
      (node (ref "XMEGA64") (pin "10") (pinfunction "PB4_10") (pintype "bidirectional"))
    )
    (net (code "88") (name "unconnected-(XMEGA64-PB5-Pad11)") (class "Default")
      (node (ref "XMEGA64") (pin "11") (pinfunction "PB5_11") (pintype "bidirectional"))
    )
    (net (code "89") (name "unconnected-(XMEGA64-PB6-Pad12)") (class "Default")
      (node (ref "XMEGA64") (pin "12") (pinfunction "PB6_12") (pintype "bidirectional"))
    )
    (net (code "90") (name "unconnected-(XMEGA64-PB7-Pad13)") (class "Default")
      (node (ref "XMEGA64") (pin "13") (pinfunction "PB7_13") (pintype "bidirectional"))
    )
    (net (code "91") (name "unconnected-(XMEGA64-PD6-Pad32)") (class "Default")
      (node (ref "XMEGA64") (pin "32") (pinfunction "PD6_32") (pintype "bidirectional"))
    )
    (net (code "92") (name "unconnected-(XMEGA64-PD7-Pad33)") (class "Default")
      (node (ref "XMEGA64") (pin "33") (pinfunction "PD7_33") (pintype "bidirectional"))
    )
    (net (code "93") (name "unconnected-(XMEGA64-PE2-Pad38)") (class "Default")
      (node (ref "XMEGA64") (pin "38") (pinfunction "PE2_38") (pintype "bidirectional"))
    )
    (net (code "94") (name "unconnected-(XMEGA64-PE3-Pad39)") (class "Default")
      (node (ref "XMEGA64") (pin "39") (pinfunction "PE3_39") (pintype "bidirectional"))
    )
  )
)
